# SNES-GamePad.net
KiCad netlist of a schematic drawn in EAGLE
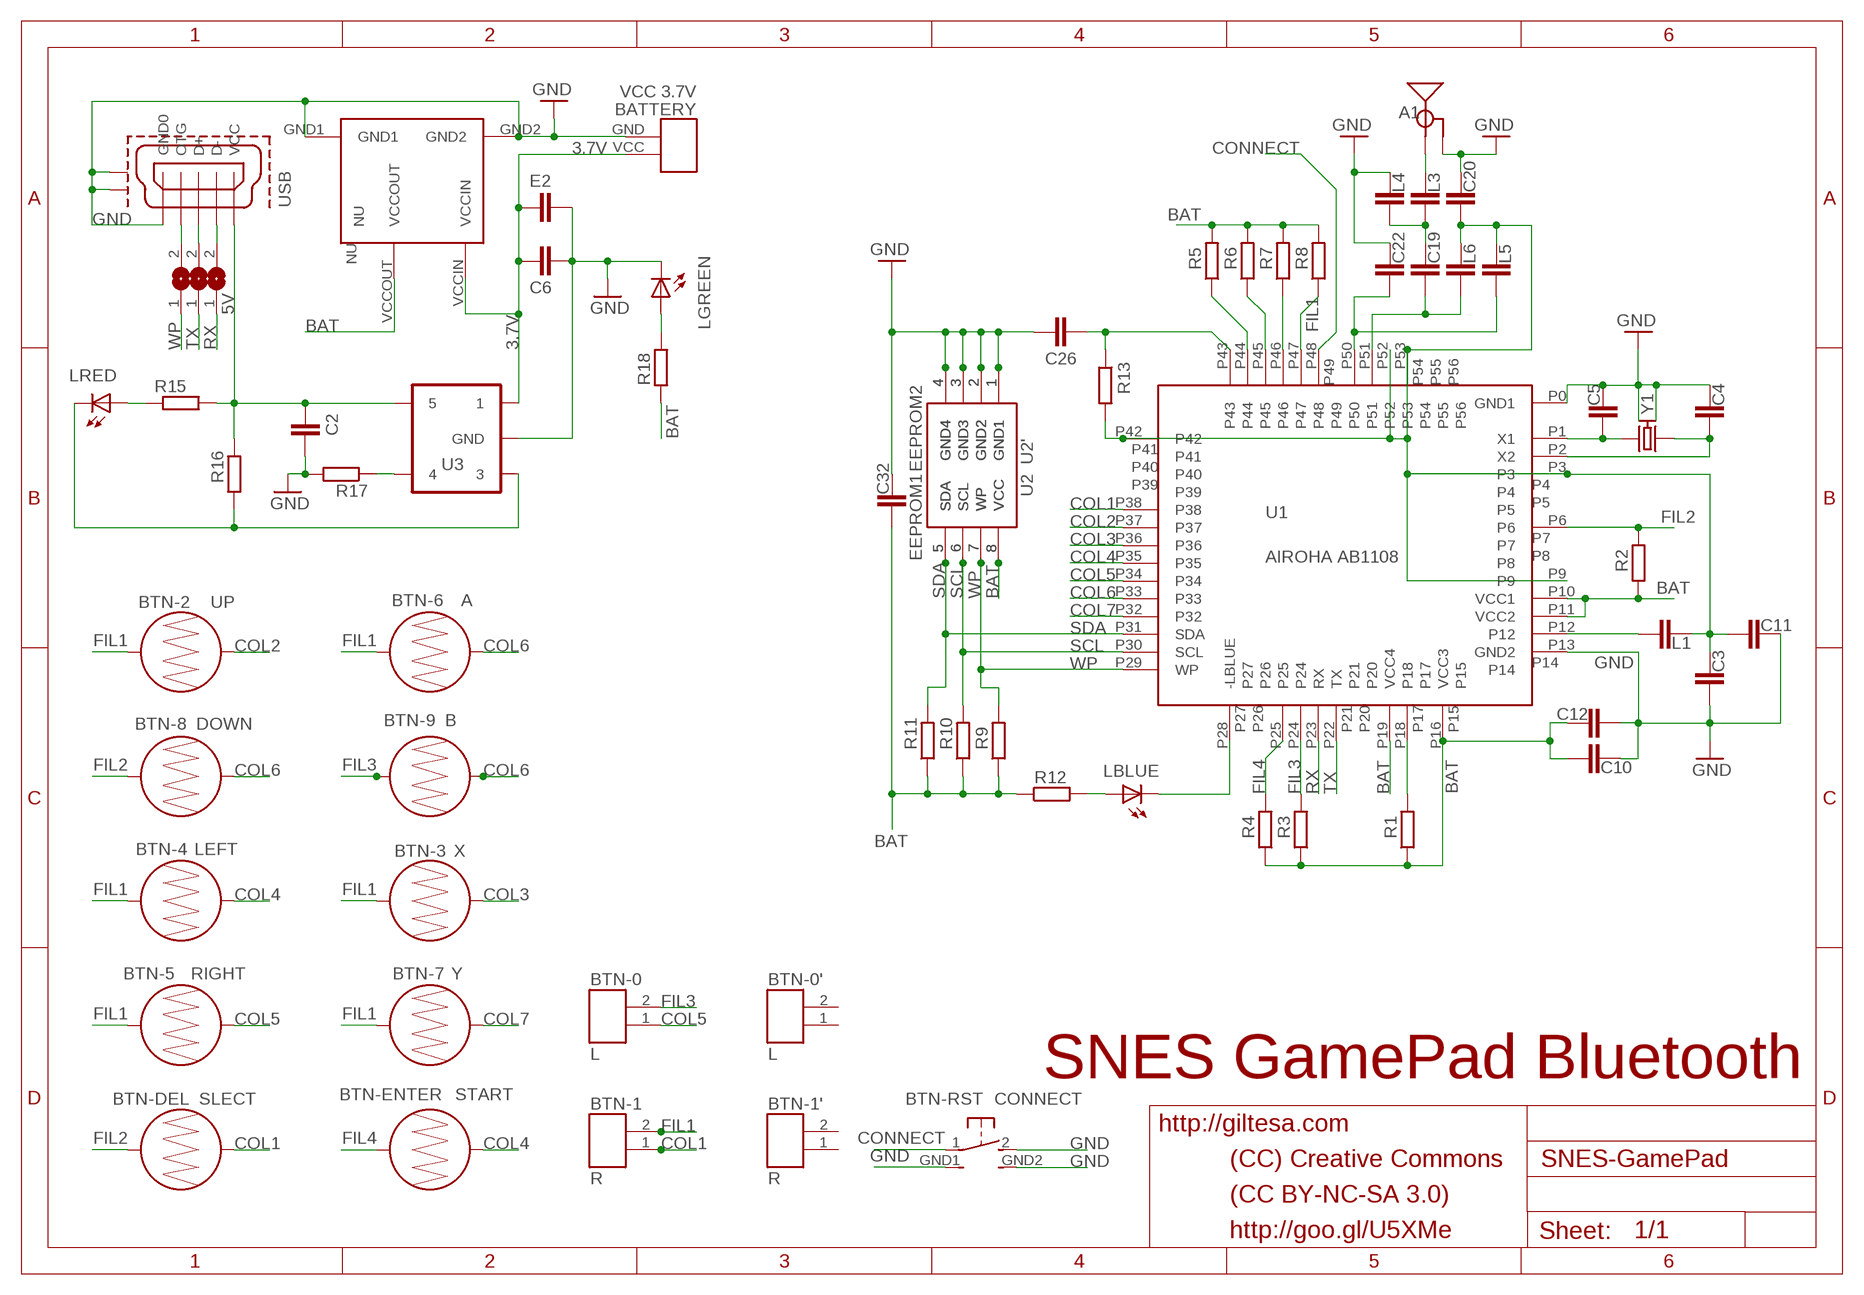
[diagram p0: schematic, sheet 1]

(export (version "E")
  (design (tool "Eeschema 10.0.6"))
  (components
    (comp (ref "A1")
      (value "ANTENA")
      (footprint "eagle-import:ANTENA-AIROHA")
      (libsource (lib "eagle-import") (part "ANTENA-AIROHA"))
    )
    (comp (ref "BATTERY")
      (value "VCC 3.7V")
      (footprint "eagle-import:1X02_SMD_BIG")
      (libsource (lib "eagle-import") (part "1X02_SMD_BIG"))
    )
    (comp (ref "BTN-0")
      (value "L")
      (footprint "eagle-import:1X02_SMD")
      (libsource (lib "eagle-import") (part "1X02_SMD"))
    )
    (comp (ref "BTN-0'")
      (value "L")
      (footprint "eagle-import:SNES_GAMEPAD_RL")
      (libsource (lib "eagle-import") (part "SNES_GAMEPAD_RL"))
    )
    (comp (ref "BTN-1")
      (value "R")
      (footprint "eagle-import:1X02_SMD")
      (libsource (lib "eagle-import") (part "1X02_SMD"))
    )
    (comp (ref "BTN-1'")
      (value "R")
      (footprint "eagle-import:SNES_GAMEPAD_RL")
      (libsource (lib "eagle-import") (part "SNES_GAMEPAD_RL"))
    )
    (comp (ref "BTN-2")
      (value "UP")
      (footprint "eagle-import:BUTTON-CONDUCTIVE-PAD")
      (libsource (lib "eagle-import") (part "BUTTON-CONDUCTIVE-PAD"))
    )
    (comp (ref "BTN-3")
      (value "X")
      (footprint "eagle-import:BUTTON-CONDUCTIVE-BUTTON")
      (libsource (lib "eagle-import") (part "BUTTON-CONDUCTIVE-BUTTON"))
    )
    (comp (ref "BTN-4")
      (value "LEFT")
      (footprint "eagle-import:BUTTON-CONDUCTIVE-PAD")
      (libsource (lib "eagle-import") (part "BUTTON-CONDUCTIVE-PAD"))
    )
    (comp (ref "BTN-5")
      (value "RIGHT")
      (footprint "eagle-import:BUTTON-CONDUCTIVE-PAD")
      (libsource (lib "eagle-import") (part "BUTTON-CONDUCTIVE-PAD"))
    )
    (comp (ref "BTN-6")
      (value "A")
      (footprint "eagle-import:BUTTON-CONDUCTIVE-BUTTON")
      (libsource (lib "eagle-import") (part "BUTTON-CONDUCTIVE-BUTTON"))
    )
    (comp (ref "BTN-7")
      (value "Y")
      (footprint "eagle-import:BUTTON-CONDUCTIVE-BUTTON")
      (libsource (lib "eagle-import") (part "BUTTON-CONDUCTIVE-BUTTON"))
    )
    (comp (ref "BTN-8")
      (value "DOWN")
      (footprint "eagle-import:BUTTON-CONDUCTIVE-PAD")
      (libsource (lib "eagle-import") (part "BUTTON-CONDUCTIVE-PAD"))
    )
    (comp (ref "BTN-9")
      (value "B")
      (footprint "eagle-import:BUTTON-CONDUCTIVE-BUTTON")
      (libsource (lib "eagle-import") (part "BUTTON-CONDUCTIVE-BUTTON"))
    )
    (comp (ref "BTN-DEL")
      (value "SLECT")
      (footprint "eagle-import:BUTTON-CONDUCTIVE-BUTTON")
      (libsource (lib "eagle-import") (part "BUTTON-CONDUCTIVE-BUTTON"))
    )
    (comp (ref "BTN-ENTER")
      (value "START")
      (footprint "eagle-import:BUTTON-CONDUCTIVE-BUTTON")
      (libsource (lib "eagle-import") (part "BUTTON-CONDUCTIVE-BUTTON"))
    )
    (comp (ref "BTN-RST")
      (value "CONNECT")
      (footprint "eagle-import:SWITCH-90º")
      (libsource (lib "eagle-import") (part "SWITCH-90º"))
    )
    (comp (ref "C2")
      (value "C0603")
      (footprint "eagle-import:C0603")
      (libsource (lib "eagle-import") (part "C0603"))
    )
    (comp (ref "C3")
      (value "C0603")
      (footprint "eagle-import:C0603")
      (libsource (lib "eagle-import") (part "C0603"))
    )
    (comp (ref "C4")
      (value "C0603")
      (footprint "eagle-import:C0603")
      (libsource (lib "eagle-import") (part "C0603"))
    )
    (comp (ref "C5")
      (value "C0603")
      (footprint "eagle-import:C0603")
      (libsource (lib "eagle-import") (part "C0603"))
    )
    (comp (ref "C6")
      (value "C0603")
      (footprint "eagle-import:C0603")
      (libsource (lib "eagle-import") (part "C0603"))
    )
    (comp (ref "C10")
      (value "C0603")
      (footprint "eagle-import:C0603")
      (libsource (lib "eagle-import") (part "C0603"))
    )
    (comp (ref "C11")
      (value "C0603")
      (footprint "eagle-import:C0603")
      (libsource (lib "eagle-import") (part "C0603"))
    )
    (comp (ref "C12")
      (value "C0603")
      (footprint "eagle-import:C0603")
      (libsource (lib "eagle-import") (part "C0603"))
    )
    (comp (ref "C19")
      (value "C0603")
      (footprint "eagle-import:C0603")
      (libsource (lib "eagle-import") (part "C0603"))
    )
    (comp (ref "C20")
      (value "C0603")
      (footprint "eagle-import:C0603")
      (libsource (lib "eagle-import") (part "C0603"))
    )
    (comp (ref "C22")
      (value "C0603")
      (footprint "eagle-import:C0603")
      (libsource (lib "eagle-import") (part "C0603"))
    )
    (comp (ref "C26")
      (value "C0603")
      (footprint "eagle-import:C0603")
      (libsource (lib "eagle-import") (part "C0603"))
    )
    (comp (ref "C32")
      (value "C0603")
      (footprint "eagle-import:C0603")
      (libsource (lib "eagle-import") (part "C0603"))
    )
    (comp (ref "E2")
      (value "C0805")
      (footprint "eagle-import:C0805")
      (libsource (lib "eagle-import") (part "C0805"))
    )
    (comp (ref "L1")
      (value "C1206")
      (footprint "eagle-import:C1206")
      (libsource (lib "eagle-import") (part "C1206"))
    )
    (comp (ref "L3")
      (value "C0603")
      (footprint "eagle-import:C0603")
      (libsource (lib "eagle-import") (part "C0603"))
    )
    (comp (ref "L4")
      (value "C0603")
      (footprint "eagle-import:C0603")
      (libsource (lib "eagle-import") (part "C0603"))
    )
    (comp (ref "L5")
      (value "C0603")
      (footprint "eagle-import:C0603")
      (libsource (lib "eagle-import") (part "C0603"))
    )
    (comp (ref "L6")
      (value "C0603")
      (footprint "eagle-import:C0603")
      (libsource (lib "eagle-import") (part "C0603"))
    )
    (comp (ref "LBLUE")
      (value "LEDCHIPLED_0805")
      (footprint "eagle-import:CHIPLED_0805")
      (libsource (lib "eagle-import") (part "LEDCHIPLED_0805"))
    )
    (comp (ref "LGREEN")
      (value "LEDCHIPLED_0805")
      (footprint "eagle-import:CHIPLED_0805")
      (libsource (lib "eagle-import") (part "LEDCHIPLED_0805"))
    )
    (comp (ref "LRED")
      (value "LEDCHIPLED_0805")
      (footprint "eagle-import:CHIPLED_0805")
      (libsource (lib "eagle-import") (part "LEDCHIPLED_0805"))
    )
    (comp (ref "R1")
      (value "22kΩ")
      (footprint "eagle-import:R0603")
      (libsource (lib "eagle-import") (part "R0603"))
    )
    (comp (ref "R2")
      (value "22kΩ")
      (footprint "eagle-import:R0603")
      (libsource (lib "eagle-import") (part "R0603"))
    )
    (comp (ref "R3")
      (value "22kΩ")
      (footprint "eagle-import:R0603")
      (libsource (lib "eagle-import") (part "R0603"))
    )
    (comp (ref "R4")
      (value "22kΩ")
      (footprint "eagle-import:R0603")
      (libsource (lib "eagle-import") (part "R0603"))
    )
    (comp (ref "R5")
      (value "22kΩ")
      (footprint "eagle-import:R0603")
      (libsource (lib "eagle-import") (part "R0603"))
    )
    (comp (ref "R6")
      (value "22kΩ")
      (footprint "eagle-import:R0603")
      (libsource (lib "eagle-import") (part "R0603"))
    )
    (comp (ref "R7")
      (value "22kΩ")
      (footprint "eagle-import:R0603")
      (libsource (lib "eagle-import") (part "R0603"))
    )
    (comp (ref "R8")
      (value "22kΩ")
      (footprint "eagle-import:R0603")
      (libsource (lib "eagle-import") (part "R0603"))
    )
    (comp (ref "R9")
      (value "4.7kΩ")
      (footprint "eagle-import:R0603")
      (libsource (lib "eagle-import") (part "R0603"))
    )
    (comp (ref "R10")
      (value "2.2kΩ")
      (footprint "eagle-import:R0603")
      (libsource (lib "eagle-import") (part "R0603"))
    )
    (comp (ref "R11")
      (value "2.2kΩ")
      (footprint "eagle-import:R0603")
      (libsource (lib "eagle-import") (part "R0603"))
    )
    (comp (ref "R12")
      (value "330Ω")
      (footprint "eagle-import:R0603")
      (libsource (lib "eagle-import") (part "R0603"))
    )
    (comp (ref "R13")
      (value "10Ω")
      (footprint "eagle-import:R0603")
      (libsource (lib "eagle-import") (part "R0603"))
    )
    (comp (ref "R15")
      (value "330Ω")
      (footprint "eagle-import:R0603")
      (libsource (lib "eagle-import") (part "R0603"))
    )
    (comp (ref "R16")
      (value "10kΩ")
      (footprint "eagle-import:R0603")
      (libsource (lib "eagle-import") (part "R0603"))
    )
    (comp (ref "R17")
      (value "4.7kΩ")
      (footprint "eagle-import:R0603")
      (libsource (lib "eagle-import") (part "R0603"))
    )
    (comp (ref "R18")
      (value "1kΩ")
      (footprint "eagle-import:R0603")
      (libsource (lib "eagle-import") (part "R0603"))
    )
    (comp (ref "S2")
      (value "INTERRUPTOR_1")
      (footprint "eagle-import:INTERRUPTOR_1")
      (libsource (lib "eagle-import") (part "INTERRUPTOR_1"))
    )
    (comp (ref "SJ1")
      (value "JUMPER-SMD")
      (footprint "eagle-import:JUMPER-SMD")
      (libsource (lib "eagle-import") (part "JUMPER-SMD"))
    )
    (comp (ref "SJ2")
      (value "JUMPER-SMD")
      (footprint "eagle-import:JUMPER-SMD")
      (libsource (lib "eagle-import") (part "JUMPER-SMD"))
    )
    (comp (ref "SJ3")
      (value "JUMPER-SMD")
      (footprint "eagle-import:JUMPER-SMD")
      (libsource (lib "eagle-import") (part "JUMPER-SMD"))
    )
    (comp (ref "U1")
      (value "AIROHA AB1108")
      (footprint "eagle-import:QFN56_6MM")
      (libsource (lib "eagle-import") (part "QFN56_6MM"))
    )
    (comp (ref "U2")
      (value "EEPROM1")
      (footprint "eagle-import:TSSOP8")
      (libsource (lib "eagle-import") (part "EEPROM-BLUETOOTH-SNES"))
    )
    (comp (ref "U2'")
      (value "EEPROM2")
      (footprint "eagle-import:M8-EEPROM")
      (libsource (lib "eagle-import") (part "EEPROM-BLUETOOTH-SNES2"))
    )
    (comp (ref "U3")
      (value "SOT23-5")
      (footprint "eagle-import:SOT23-5")
      (libsource (lib "eagle-import") (part "SOT23-5"))
    )
    (comp (ref "USB")
      (value "MICRO_USB_1")
      (footprint "eagle-import:MICRO_USB_1")
      (libsource (lib "eagle-import") (part "MICRO_USB_1"))
    )
    (comp (ref "Y1")
      (value "CRISTAL")
      (footprint "eagle-import:CRISTAL-SMD-3X2.5MM")
      (libsource (lib "eagle-import") (part "CRISTAL-SMD-3X2.5MM"))
    )
  )
  (nets
    (net (code "1") (name "/3.7V") (class "Default")
      (node (ref "BATTERY") (pin "VCC") (pinfunction "VCC_VCC") (pintype "passive"))
      (node (ref "C6") (pin "1") (pinfunction "1_1") (pintype "passive"))
      (node (ref "E2") (pin "1") (pinfunction "1_1") (pintype "passive"))
      (node (ref "S2") (pin "VCCIN") (pinfunction "VCCIN_VCCIN") (pintype "bidirectional"))
      (node (ref "U3") (pin "1") (pinfunction "1_1") (pintype "input"))
    )
    (net (code "2") (name "/5V") (class "Default")
      (node (ref "C2") (pin "1") (pinfunction "1_1") (pintype "passive"))
      (node (ref "R15") (pin "2") (pinfunction "2_2") (pintype "passive"))
      (node (ref "R16") (pin "2") (pinfunction "2_2") (pintype "passive"))
      (node (ref "U3") (pin "5") (pinfunction "5_5") (pintype "passive"))
      (node (ref "USB") (pin "VCC") (pinfunction "VCC_VCC") (pintype "input"))
    )
    (net (code "3") (name "/BAT") (class "Default")
      (node (ref "C10") (pin "1") (pinfunction "1_1") (pintype "passive"))
      (node (ref "C12") (pin "1") (pinfunction "1_1") (pintype "passive"))
      (node (ref "C32") (pin "2") (pinfunction "2_2") (pintype "passive"))
      (node (ref "R1") (pin "1") (pinfunction "1_1") (pintype "passive"))
      (node (ref "R10") (pin "1") (pinfunction "1_1") (pintype "passive"))
      (node (ref "R11") (pin "1") (pinfunction "1_1") (pintype "passive"))
      (node (ref "R12") (pin "1") (pinfunction "1_1") (pintype "passive"))
      (node (ref "R18") (pin "2") (pinfunction "2_2") (pintype "passive"))
      (node (ref "R2") (pin "1") (pinfunction "1_1") (pintype "passive"))
      (node (ref "R3") (pin "1") (pinfunction "1_1") (pintype "passive"))
      (node (ref "R4") (pin "1") (pinfunction "1_1") (pintype "passive"))
      (node (ref "R5") (pin "2") (pinfunction "2_2") (pintype "passive"))
      (node (ref "R6") (pin "2") (pinfunction "2_2") (pintype "passive"))
      (node (ref "R7") (pin "2") (pinfunction "2_2") (pintype "passive"))
      (node (ref "R8") (pin "2") (pinfunction "2_2") (pintype "passive"))
      (node (ref "R9") (pin "1") (pinfunction "1_1") (pintype "passive"))
      (node (ref "S2") (pin "VCCOUT") (pinfunction "VCCOUT_VCCOUT") (pintype "bidirectional"))
      (node (ref "U1") (pin "P10") (pinfunction "VCC1_P10") (pintype "bidirectional"))
      (node (ref "U1") (pin "P11") (pinfunction "VCC2_P11") (pintype "bidirectional"))
      (node (ref "U1") (pin "P16") (pinfunction "VCC3_P16") (pintype "bidirectional"))
      (node (ref "U1") (pin "P19") (pinfunction "VCC4_P19") (pintype "bidirectional"))
      (node (ref "U2") (pin "8") (pinfunction "VCC_8") (pintype "bidirectional"))
      (node (ref "U2'") (pin "8") (pinfunction "VCC_8") (pintype "bidirectional"))
    )
    (net (code "4") (name "/COL1") (class "Default")
      (node (ref "BTN-1") (pin "1") (pinfunction "1_1") (pintype "passive"))
      (node (ref "BTN-DEL") (pin "2") (pinfunction "2_2") (pintype "passive"))
      (node (ref "U1") (pin "P38") (pinfunction "P38_P38") (pintype "bidirectional"))
    )
    (net (code "5") (name "/COL2") (class "Default")
      (node (ref "BTN-2") (pin "2") (pinfunction "2_2") (pintype "passive"))
      (node (ref "U1") (pin "P37") (pinfunction "P37_P37") (pintype "bidirectional"))
    )
    (net (code "6") (name "/COL3") (class "Default")
      (node (ref "BTN-3") (pin "1") (pinfunction "1_1") (pintype "passive"))
      (node (ref "U1") (pin "P36") (pinfunction "P36_P36") (pintype "bidirectional"))
    )
    (net (code "7") (name "/COL4") (class "Default")
      (node (ref "BTN-4") (pin "1") (pinfunction "1_1") (pintype "passive"))
      (node (ref "BTN-ENTER") (pin "1") (pinfunction "1_1") (pintype "passive"))
      (node (ref "U1") (pin "P35") (pinfunction "P35_P35") (pintype "bidirectional"))
    )
    (net (code "8") (name "/COL5") (class "Default")
      (node (ref "BTN-0") (pin "1") (pinfunction "1_1") (pintype "passive"))
      (node (ref "BTN-5") (pin "2") (pinfunction "2_2") (pintype "passive"))
      (node (ref "U1") (pin "P34") (pinfunction "P34_P34") (pintype "bidirectional"))
    )
    (net (code "9") (name "/COL6") (class "Default")
      (node (ref "BTN-6") (pin "2") (pinfunction "2_2") (pintype "passive"))
      (node (ref "BTN-8") (pin "2") (pinfunction "2_2") (pintype "passive"))
      (node (ref "BTN-9") (pin "2") (pinfunction "2_2") (pintype "passive"))
      (node (ref "U1") (pin "P33") (pinfunction "P33_P33") (pintype "bidirectional"))
    )
    (net (code "10") (name "/COL7") (class "Default")
      (node (ref "BTN-7") (pin "2") (pinfunction "2_2") (pintype "passive"))
      (node (ref "U1") (pin "P32") (pinfunction "P32_P32") (pintype "bidirectional"))
    )
    (net (code "11") (name "/CONNECT") (class "Default")
      (node (ref "BTN-RST") (pin "1") (pinfunction "1_1") (pintype "passive"))
      (node (ref "U1") (pin "P48") (pinfunction "P48_P48") (pintype "bidirectional"))
    )
    (net (code "12") (name "/FIL1") (class "Default")
      (node (ref "BTN-1") (pin "2") (pinfunction "2_2") (pintype "passive"))
      (node (ref "BTN-2") (pin "1") (pinfunction "1_1") (pintype "passive"))
      (node (ref "BTN-3") (pin "2") (pinfunction "2_2") (pintype "passive"))
      (node (ref "BTN-4") (pin "2") (pinfunction "2_2") (pintype "passive"))
      (node (ref "BTN-5") (pin "1") (pinfunction "1_1") (pintype "passive"))
      (node (ref "BTN-6") (pin "1") (pinfunction "1_1") (pintype "passive"))
      (node (ref "BTN-7") (pin "1") (pinfunction "1_1") (pintype "passive"))
      (node (ref "R8") (pin "1") (pinfunction "1_1") (pintype "passive"))
      (node (ref "U1") (pin "P47") (pinfunction "P47_P47") (pintype "bidirectional"))
    )
    (net (code "13") (name "/FIL2") (class "Default")
      (node (ref "BTN-8") (pin "1") (pinfunction "1_1") (pintype "passive"))
      (node (ref "BTN-DEL") (pin "1") (pinfunction "1_1") (pintype "passive"))
      (node (ref "R2") (pin "2") (pinfunction "2_2") (pintype "passive"))
      (node (ref "U1") (pin "P6") (pinfunction "P6_P6") (pintype "bidirectional"))
    )
    (net (code "14") (name "/FIL3") (class "Default")
      (node (ref "BTN-0") (pin "2") (pinfunction "2_2") (pintype "passive"))
      (node (ref "BTN-9") (pin "1") (pinfunction "1_1") (pintype "passive"))
      (node (ref "R3") (pin "2") (pinfunction "2_2") (pintype "passive"))
      (node (ref "U1") (pin "P24") (pinfunction "P24_P24") (pintype "bidirectional"))
    )
    (net (code "15") (name "/FIL4") (class "Default")
      (node (ref "BTN-ENTER") (pin "2") (pinfunction "2_2") (pintype "passive"))
      (node (ref "R4") (pin "2") (pinfunction "2_2") (pintype "passive"))
      (node (ref "U1") (pin "P25") (pinfunction "P25_P25") (pintype "bidirectional"))
    )
    (net (code "16") (name "/RX") (class "Default")
      (node (ref "SJ3") (pin "1") (pinfunction "1_1") (pintype "passive"))
      (node (ref "U1") (pin "P23") (pinfunction "RX_P23") (pintype "bidirectional"))
    )
    (net (code "17") (name "/SCL") (class "Default")
      (node (ref "R10") (pin "2") (pinfunction "2_2") (pintype "passive"))
      (node (ref "U1") (pin "P30") (pinfunction "SCL_P30") (pintype "bidirectional"))
      (node (ref "U2") (pin "6") (pinfunction "SCL_6") (pintype "bidirectional"))
      (node (ref "U2'") (pin "6") (pinfunction "SCL_6") (pintype "bidirectional"))
    )
    (net (code "18") (name "/SDA") (class "Default")
      (node (ref "R11") (pin "2") (pinfunction "2_2") (pintype "passive"))
      (node (ref "U1") (pin "P31") (pinfunction "SDA_P31") (pintype "bidirectional"))
      (node (ref "U2") (pin "5") (pinfunction "SDA_5") (pintype "bidirectional"))
      (node (ref "U2'") (pin "5") (pinfunction "SDA_5") (pintype "bidirectional"))
    )
    (net (code "19") (name "/TX") (class "Default")
      (node (ref "SJ2") (pin "1") (pinfunction "1_1") (pintype "passive"))
      (node (ref "U1") (pin "P22") (pinfunction "TX_P22") (pintype "bidirectional"))
    )
    (net (code "20") (name "/WP") (class "Default")
      (node (ref "R9") (pin "2") (pinfunction "2_2") (pintype "passive"))
      (node (ref "SJ1") (pin "1") (pinfunction "1_1") (pintype "passive"))
      (node (ref "U1") (pin "P29") (pinfunction "WP_P29") (pintype "bidirectional"))
      (node (ref "U2") (pin "7") (pinfunction "WP_7") (pintype "bidirectional"))
      (node (ref "U2'") (pin "7") (pinfunction "WP_7") (pintype "bidirectional"))
    )
    (net (code "21") (name "GND") (class "Default")
      (node (ref "A1") (pin "GND") (pinfunction "GND_GND") (pintype "bidirectional"))
      (node (ref "BATTERY") (pin "GND") (pinfunction "GND_GND") (pintype "passive"))
      (node (ref "BTN-RST") (pin "2") (pinfunction "2_2") (pintype "passive"))
      (node (ref "BTN-RST") (pin "GND1") (pinfunction "GND1_GND1") (pintype "passive"))
      (node (ref "BTN-RST") (pin "GND2") (pinfunction "GND2_GND2") (pintype "passive"))
      (node (ref "C10") (pin "2") (pinfunction "2_2") (pintype "passive"))
      (node (ref "C11") (pin "1") (pinfunction "1_1") (pintype "passive"))
      (node (ref "C12") (pin "2") (pinfunction "2_2") (pintype "passive"))
      (node (ref "C2") (pin "2") (pinfunction "2_2") (pintype "passive"))
      (node (ref "C20") (pin "1") (pinfunction "1_1") (pintype "passive"))
      (node (ref "C22") (pin "1") (pinfunction "1_1") (pintype "passive"))
      (node (ref "C26") (pin "2") (pinfunction "2_2") (pintype "passive"))
      (node (ref "C3") (pin "2") (pinfunction "2_2") (pintype "passive"))
      (node (ref "C32") (pin "1") (pinfunction "1_1") (pintype "passive"))
      (node (ref "C4") (pin "1") (pinfunction "1_1") (pintype "passive"))
      (node (ref "C5") (pin "1") (pinfunction "1_1") (pintype "passive"))
      (node (ref "C6") (pin "2") (pinfunction "2_2") (pintype "passive"))
      (node (ref "E2") (pin "2") (pinfunction "2_2") (pintype "passive"))
      (node (ref "L4") (pin "1") (pinfunction "1_1") (pintype "passive"))
      (node (ref "LGREEN") (pin "C") (pinfunction "C_C") (pintype "passive"))
      (node (ref "R17") (pin "2") (pinfunction "2_2") (pintype "passive"))
      (node (ref "S2") (pin "GND1") (pinfunction "GND1_GND1") (pintype "bidirectional"))
      (node (ref "S2") (pin "GND2") (pinfunction "GND2_GND2") (pintype "bidirectional"))
      (node (ref "U1") (pin "P0") (pinfunction "GND1_P0") (pintype "bidirectional"))
      (node (ref "U1") (pin "P13") (pinfunction "GND2_P13") (pintype "bidirectional"))
      (node (ref "U2") (pin "1") (pinfunction "GND1_1") (pintype "bidirectional"))
      (node (ref "U2") (pin "2") (pinfunction "GND2_2") (pintype "bidirectional"))
      (node (ref "U2") (pin "3") (pinfunction "GND3_3") (pintype "bidirectional"))
      (node (ref "U2") (pin "4") (pinfunction "GND4_4") (pintype "bidirectional"))
      (node (ref "U2'") (pin "1") (pinfunction "GND1_1") (pintype "bidirectional"))
      (node (ref "U2'") (pin "2") (pinfunction "GND2_2") (pintype "bidirectional"))
      (node (ref "U2'") (pin "3") (pinfunction "GND3_3") (pintype "bidirectional"))
      (node (ref "U2'") (pin "4") (pinfunction "GND4_4") (pintype "bidirectional"))
      (node (ref "U3") (pin "2") (pinfunction "GND_2") (pintype "input"))
      (node (ref "USB") (pin "GND0") (pinfunction "GND0_GND0") (pintype "input"))
      (node (ref "USB") (pin "GND1") (pinfunction "GND1_GND1") (pintype "bidirectional"))
      (node (ref "USB") (pin "GND2") (pinfunction "GND2_GND2") (pintype "bidirectional"))
      (node (ref "Y1") (pin "GND1") (pinfunction "GND1_GND1") (pintype "passive"))
      (node (ref "Y1") (pin "GND2") (pinfunction "GND2_GND2") (pintype "passive"))
    )
    (net (code "22") (name "Net-(A1-PadSIGNAL)") (class "Default")
      (node (ref "A1") (pin "SIGNAL") (pinfunction "SIGNAL_SIGNAL") (pintype "bidirectional"))
      (node (ref "L3") (pin "1") (pinfunction "1_1") (pintype "passive"))
    )
    (net (code "23") (name "Net-(C11-Pad2)") (class "Default")
      (node (ref "C11") (pin "2") (pinfunction "2_2") (pintype "passive"))
      (node (ref "C20") (pin "2") (pinfunction "2_2") (pintype "passive"))
      (node (ref "C3") (pin "1") (pinfunction "1_1") (pintype "passive"))
      (node (ref "L1") (pin "2") (pinfunction "2_2") (pintype "passive"))
      (node (ref "L5") (pin "1") (pinfunction "1_1") (pintype "passive"))
      (node (ref "L6") (pin "1") (pinfunction "1_1") (pintype "passive"))
      (node (ref "R13") (pin "2") (pinfunction "2_2") (pintype "passive"))
      (node (ref "U1") (pin "P3") (pinfunction "P3_P3") (pintype "bidirectional"))
      (node (ref "U1") (pin "P42") (pinfunction "P42_P42") (pintype "bidirectional"))
      (node (ref "U1") (pin "P52") (pinfunction "P52_P52") (pintype "bidirectional"))
      (node (ref "U1") (pin "P53") (pinfunction "P53_P53") (pintype "bidirectional"))
      (node (ref "U1") (pin "P9") (pinfunction "P9_P9") (pintype "bidirectional"))
    )
    (net (code "24") (name "Net-(C19-Pad1)") (class "Default")
      (node (ref "C19") (pin "1") (pinfunction "1_1") (pintype "passive"))
      (node (ref "L3") (pin "2") (pinfunction "2_2") (pintype "passive"))
      (node (ref "L4") (pin "2") (pinfunction "2_2") (pintype "passive"))
    )
    (net (code "25") (name "Net-(C19-Pad2)") (class "Default")
      (node (ref "C19") (pin "2") (pinfunction "2_2") (pintype "passive"))
      (node (ref "L6") (pin "2") (pinfunction "2_2") (pintype "passive"))
      (node (ref "U1") (pin "P51") (pinfunction "P51_P51") (pintype "bidirectional"))
    )
    (net (code "26") (name "Net-(C22-Pad2)") (class "Default")
      (node (ref "C22") (pin "2") (pinfunction "2_2") (pintype "passive"))
      (node (ref "L5") (pin "2") (pinfunction "2_2") (pintype "passive"))
      (node (ref "U1") (pin "P50") (pinfunction "P50_P50") (pintype "bidirectional"))
    )
    (net (code "27") (name "Net-(C26-Pad1)") (class "Default")
      (node (ref "C26") (pin "1") (pinfunction "1_1") (pintype "passive"))
      (node (ref "R13") (pin "1") (pinfunction "1_1") (pintype "passive"))
      (node (ref "U1") (pin "P43") (pinfunction "P43_P43") (pintype "bidirectional"))
    )
    (net (code "28") (name "Net-(L1-Pad1)") (class "Default")
      (node (ref "L1") (pin "1") (pinfunction "1_1") (pintype "passive"))
      (node (ref "U1") (pin "P12") (pinfunction "P12_P12") (pintype "bidirectional"))
    )
    (net (code "29") (name "Net-(LBLUE-PadA)") (class "Default")
      (node (ref "LBLUE") (pin "A") (pinfunction "A_A") (pintype "passive"))
      (node (ref "R12") (pin "2") (pinfunction "2_2") (pintype "passive"))
    )
    (net (code "30") (name "Net-(LGREEN-PadA)") (class "Default")
      (node (ref "LGREEN") (pin "A") (pinfunction "A_A") (pintype "passive"))
      (node (ref "R18") (pin "1") (pinfunction "1_1") (pintype "passive"))
    )
    (net (code "31") (name "Net-(LRED-PadA)") (class "Default")
      (node (ref "LRED") (pin "A") (pinfunction "A_A") (pintype "passive"))
      (node (ref "R15") (pin "1") (pinfunction "1_1") (pintype "passive"))
    )
    (net (code "32") (name "Net-(LRED-PadC)") (class "Default")
      (node (ref "LRED") (pin "C") (pinfunction "C_C") (pintype "passive"))
      (node (ref "R16") (pin "1") (pinfunction "1_1") (pintype "passive"))
      (node (ref "U3") (pin "3") (pinfunction "3_3") (pintype "input"))
    )
    (net (code "33") (name "Net-(R1-Pad2)") (class "Default")
      (node (ref "R1") (pin "2") (pinfunction "2_2") (pintype "passive"))
      (node (ref "U1") (pin "P18") (pinfunction "P18_P18") (pintype "bidirectional"))
    )
    (net (code "34") (name "Net-(R5-Pad1)") (class "Default")
      (node (ref "R5") (pin "1") (pinfunction "1_1") (pintype "passive"))
      (node (ref "U1") (pin "P44") (pinfunction "P44_P44") (pintype "bidirectional"))
    )
    (net (code "35") (name "Net-(R6-Pad1)") (class "Default")
      (node (ref "R6") (pin "1") (pinfunction "1_1") (pintype "passive"))
      (node (ref "U1") (pin "P45") (pinfunction "P45_P45") (pintype "bidirectional"))
    )
    (net (code "36") (name "Net-(R7-Pad1)") (class "Default")
      (node (ref "R7") (pin "1") (pinfunction "1_1") (pintype "passive"))
      (node (ref "U1") (pin "P46") (pinfunction "P46_P46") (pintype "bidirectional"))
    )
    (net (code "37") (name "Net-(R17-Pad1)") (class "Default")
      (node (ref "R17") (pin "1") (pinfunction "1_1") (pintype "passive"))
      (node (ref "U3") (pin "4") (pinfunction "4_4") (pintype "input"))
    )
    (net (code "38") (name "Net-(SJ1-Pad2)") (class "Default")
      (node (ref "SJ1") (pin "2") (pinfunction "2_2") (pintype "passive"))
      (node (ref "USB") (pin "OTG") (pinfunction "OTG_OTG") (pintype "input"))
    )
    (net (code "39") (name "Net-(SJ2-Pad2)") (class "Default")
      (node (ref "SJ2") (pin "2") (pinfunction "2_2") (pintype "passive"))
      (node (ref "USB") (pin "D+") (pinfunction "D+_D+") (pintype "input"))
    )
    (net (code "40") (name "Net-(SJ3-Pad2)") (class "Default")
      (node (ref "SJ3") (pin "2") (pinfunction "2_2") (pintype "passive"))
      (node (ref "USB") (pin "D-") (pinfunction "D-_D-") (pintype "input"))
    )
    (net (code "41") (name "Net-(U1--LBLUE)") (class "Default")
      (node (ref "LBLUE") (pin "C") (pinfunction "C_C") (pintype "passive"))
      (node (ref "U1") (pin "P28") (pinfunction "-LBLUE_P28") (pintype "bidirectional"))
    )
    (net (code "42") (name "Net-(U1-X1)") (class "Default")
      (node (ref "C5") (pin "2") (pinfunction "2_2") (pintype "passive"))
      (node (ref "U1") (pin "P1") (pinfunction "X1_P1") (pintype "bidirectional"))
      (node (ref "Y1") (pin "P2") (pinfunction "P2_P2") (pintype "passive"))
    )
    (net (code "43") (name "Net-(U1-X2)") (class "Default")
      (node (ref "C4") (pin "2") (pinfunction "2_2") (pintype "passive"))
      (node (ref "U1") (pin "P2") (pinfunction "X2_P2") (pintype "bidirectional"))
      (node (ref "Y1") (pin "P1") (pinfunction "P1_P1") (pintype "passive"))
    )
    (net (code "44") (name "unconnected-(BTN-0'-Pad1)") (class "Default")
      (node (ref "BTN-0'") (pin "1") (pinfunction "1_1") (pintype "passive"))
    )
    (net (code "45") (name "unconnected-(BTN-0'-Pad2)") (class "Default")
      (node (ref "BTN-0'") (pin "2") (pinfunction "2_2") (pintype "passive"))
    )
    (net (code "46") (name "unconnected-(BTN-1'-Pad1)") (class "Default")
      (node (ref "BTN-1'") (pin "1") (pinfunction "1_1") (pintype "passive"))
    )
    (net (code "47") (name "unconnected-(BTN-1'-Pad2)") (class "Default")
      (node (ref "BTN-1'") (pin "2") (pinfunction "2_2") (pintype "passive"))
    )
    (net (code "48") (name "unconnected-(S2-PadNU)") (class "Default")
      (node (ref "S2") (pin "NU") (pinfunction "NU_NU") (pintype "bidirectional"))
    )
    (net (code "49") (name "unconnected-(U1-PadP4)") (class "Default")
      (node (ref "U1") (pin "P4") (pinfunction "P4_P4") (pintype "bidirectional"))
    )
    (net (code "50") (name "unconnected-(U1-PadP5)") (class "Default")
      (node (ref "U1") (pin "P5") (pinfunction "P5_P5") (pintype "bidirectional"))
    )
    (net (code "51") (name "unconnected-(U1-PadP7)") (class "Default")
      (node (ref "U1") (pin "P7") (pinfunction "P7_P7") (pintype "bidirectional"))
    )
    (net (code "52") (name "unconnected-(U1-PadP8)") (class "Default")
      (node (ref "U1") (pin "P8") (pinfunction "P8_P8") (pintype "bidirectional"))
    )
    (net (code "53") (name "unconnected-(U1-PadP14)") (class "Default")
      (node (ref "U1") (pin "P14") (pinfunction "P14_P14") (pintype "bidirectional"))
    )
    (net (code "54") (name "unconnected-(U1-PadP15)") (class "Default")
      (node (ref "U1") (pin "P15") (pinfunction "P15_P15") (pintype "bidirectional"))
    )
    (net (code "55") (name "unconnected-(U1-PadP17)") (class "Default")
      (node (ref "U1") (pin "P17") (pinfunction "P17_P17") (pintype "bidirectional"))
    )
    (net (code "56") (name "unconnected-(U1-PadP20)") (class "Default")
      (node (ref "U1") (pin "P20") (pinfunction "P20_P20") (pintype "bidirectional"))
    )
    (net (code "57") (name "unconnected-(U1-PadP21)") (class "Default")
      (node (ref "U1") (pin "P21") (pinfunction "P21_P21") (pintype "bidirectional"))
    )
    (net (code "58") (name "unconnected-(U1-PadP26)") (class "Default")
      (node (ref "U1") (pin "P26") (pinfunction "P26_P26") (pintype "bidirectional"))
    )
    (net (code "59") (name "unconnected-(U1-PadP27)") (class "Default")
      (node (ref "U1") (pin "P27") (pinfunction "P27_P27") (pintype "bidirectional"))
    )
    (net (code "60") (name "unconnected-(U1-PadP39)") (class "Default")
      (node (ref "U1") (pin "P39") (pinfunction "P39_P39") (pintype "bidirectional"))
    )
    (net (code "61") (name "unconnected-(U1-PadP40)") (class "Default")
      (node (ref "U1") (pin "P40") (pinfunction "P40_P40") (pintype "bidirectional"))
    )
    (net (code "62") (name "unconnected-(U1-PadP41)") (class "Default")
      (node (ref "U1") (pin "P41") (pinfunction "P41_P41") (pintype "bidirectional"))
    )
    (net (code "63") (name "unconnected-(U1-PadP49)") (class "Default")
      (node (ref "U1") (pin "P49") (pinfunction "P49_P49") (pintype "bidirectional"))
    )
    (net (code "64") (name "unconnected-(U1-PadP54)") (class "Default")
      (node (ref "U1") (pin "P54") (pinfunction "P54_P54") (pintype "bidirectional"))
    )
    (net (code "65") (name "unconnected-(U1-PadP55)") (class "Default")
      (node (ref "U1") (pin "P55") (pinfunction "P55_P55") (pintype "bidirectional"))
    )
    (net (code "66") (name "unconnected-(U1-PadP56)") (class "Default")
      (node (ref "U1") (pin "P56") (pinfunction "P56_P56") (pintype "bidirectional"))
    )
  )
)
